# rev2.net
KiCad netlist of a schematic drawn in EAGLE
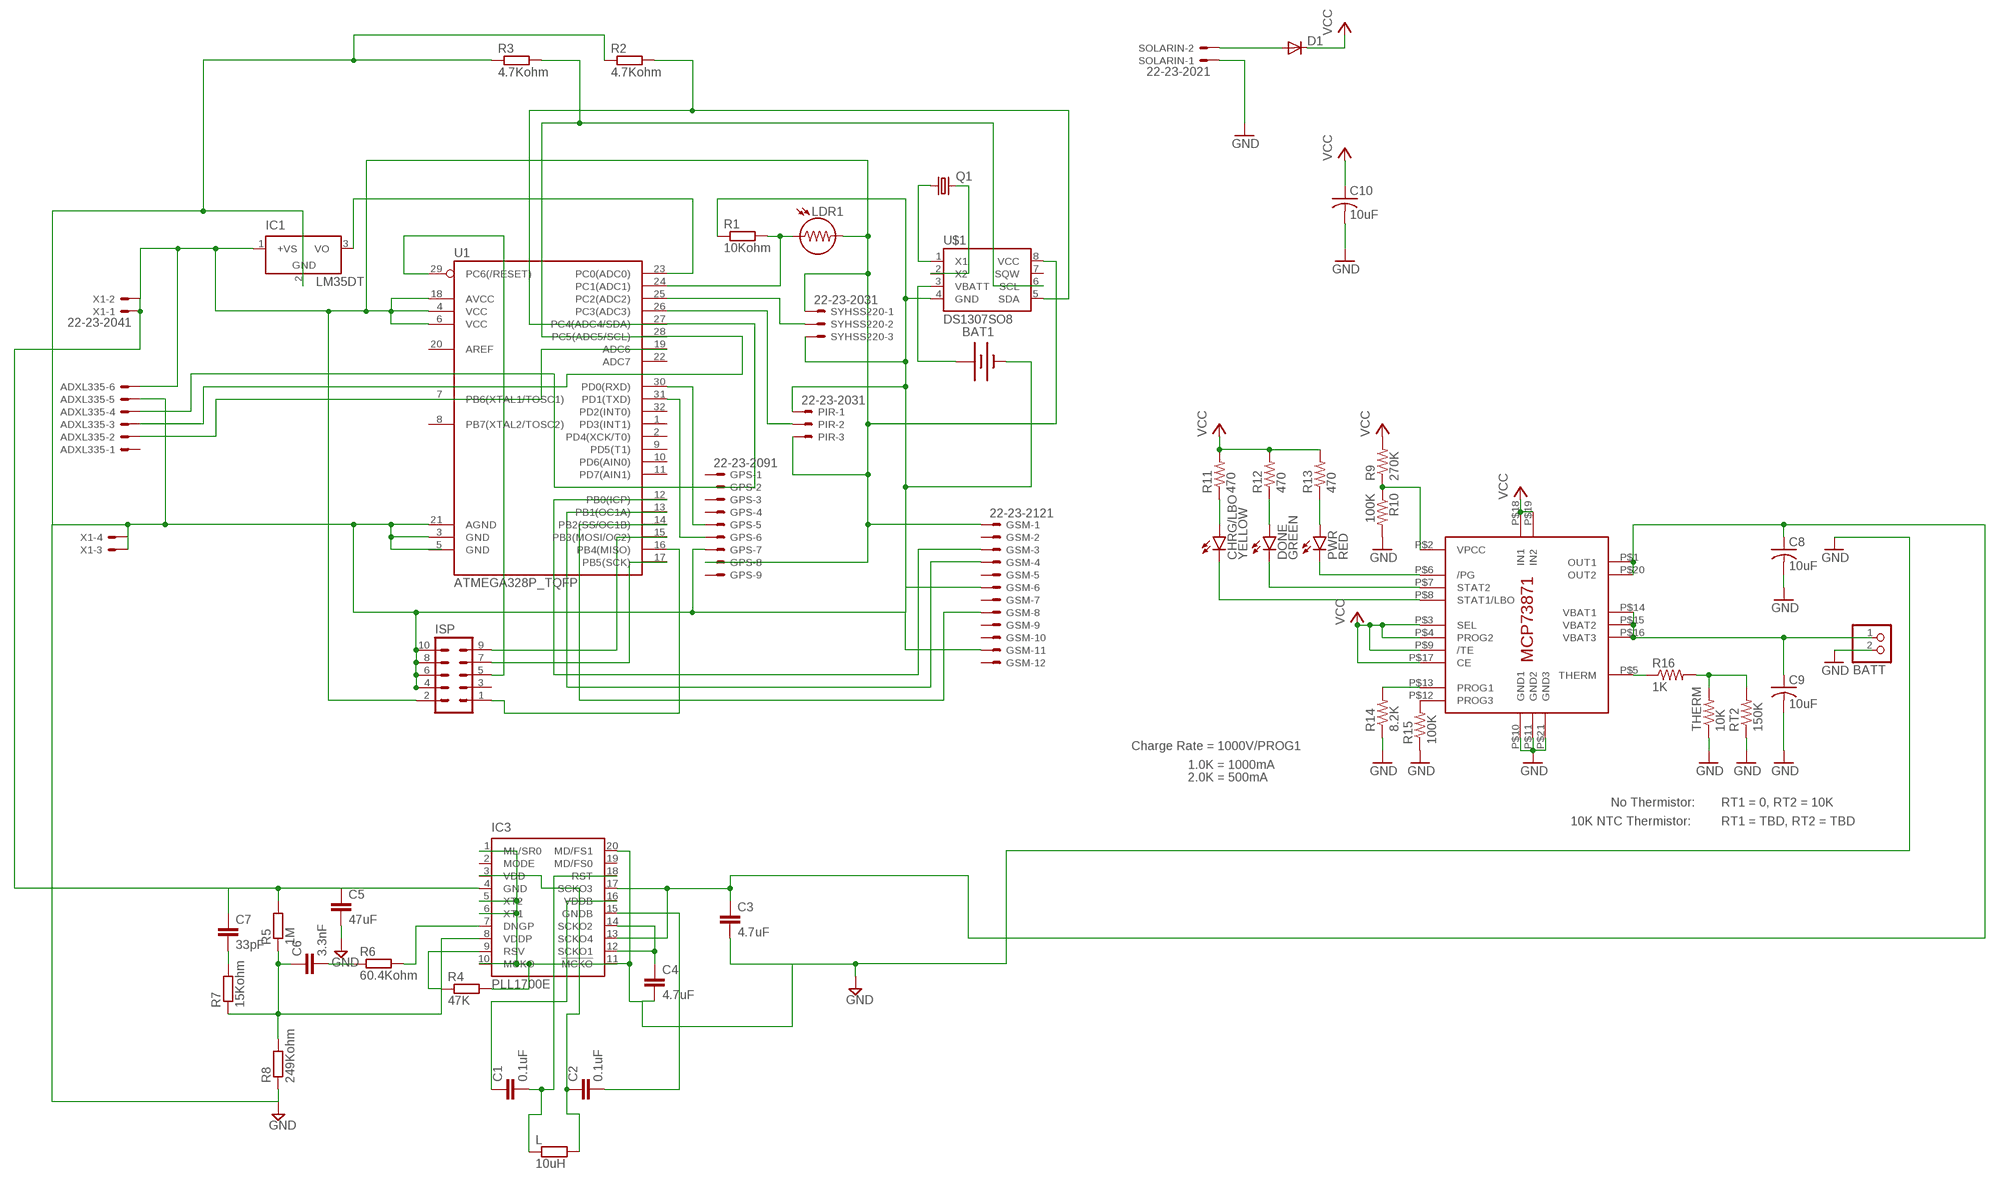
[diagram p0: schematic, sheet 1]

(export (version "E")
  (design (tool "Eeschema 10.0.6"))
  (components
    (comp (ref "ADXL335")
      (value "22-23-2061")
      (footprint "eagle-import:22-23-2061")
      (fields (field (name "MF") "MOLEX"))
      (libsource (lib "eagle-import") (part "22-23-2061"))
    )
    (comp (ref "BAT1")
      (value "BATTERY20PTH")
      (footprint "eagle-import:BATTCOM_20MM_PTH")
      (libsource (lib "eagle-import") (part "BATTERY20PTH"))
    )
    (comp (ref "BATT")
      (value "JST_2PIN-SMT-RA")
      (footprint "eagle-import:JST-PH-2-SMT-RA")
      (libsource (lib "eagle-import") (part "JST_2PIN-SMT-RA"))
    )
    (comp (ref "C1")
      (value "0.1uF")
      (footprint "eagle-import:0402-CAP")
      (libsource (lib "eagle-import") (part "0.1UF-16V(+-10%)(0402)"))
    )
    (comp (ref "C2")
      (value "0.1uF")
      (footprint "eagle-import:0402-CAP")
      (libsource (lib "eagle-import") (part "0.1UF-16V(+-10%)(0402)"))
    )
    (comp (ref "C3")
      (value "4.7uF")
      (footprint "eagle-import:0603-CAP")
      (libsource (lib "eagle-import") (part "4.7UF-6.3V-10%(0603)0603"))
    )
    (comp (ref "C4")
      (value "4.7uF")
      (footprint "eagle-import:0603-CAP")
      (libsource (lib "eagle-import") (part "4.7UF-6.3V-10%(0603)0603"))
    )
    (comp (ref "C5")
      (value "47uF")
      (footprint "eagle-import:0603-CAP")
      (libsource (lib "eagle-import") (part "CAP0603-CAP"))
    )
    (comp (ref "C6")
      (value "3.3nF")
      (footprint "eagle-import:0603-CAP")
      (libsource (lib "eagle-import") (part "3.3NF-100V-10%(0603)"))
    )
    (comp (ref "C7")
      (value "33pF")
      (footprint "eagle-import:0603-CAP")
      (libsource (lib "eagle-import") (part "33PF-50V-5%-(0603)"))
    )
    (comp (ref "C8")
      (value "10uF")
      (footprint "eagle-import:C0805K")
      (libsource (lib "eagle-import") (part "C-USC0805K"))
    )
    (comp (ref "C9")
      (value "10uF")
      (footprint "eagle-import:C0805K")
      (libsource (lib "eagle-import") (part "C-USC0805K"))
    )
    (comp (ref "C10")
      (value "10uF")
      (footprint "eagle-import:C0805K")
      (libsource (lib "eagle-import") (part "C-USC0805K"))
    )
    (comp (ref "CHRG/LBO")
      (value "YELLOW")
      (footprint "eagle-import:LED-1206")
      (libsource (lib "eagle-import") (part "LED-YELLOWLARGE"))
    )
    (comp (ref "D1")
      (value "DIODEPTH")
      (footprint "eagle-import:DIODE-1N4001")
      (libsource (lib "eagle-import") (part "DIODEPTH"))
    )
    (comp (ref "DONE")
      (value "GREEN")
      (footprint "eagle-import:LED-1206")
      (libsource (lib "eagle-import") (part "LED-GREENLARGE"))
    )
    (comp (ref "GPS")
      (value "22-23-2091")
      (footprint "eagle-import:22-23-2091")
      (fields (field (name "MF") "MOLEX"))
      (libsource (lib "eagle-import") (part "22-23-2091"))
    )
    (comp (ref "GSM")
      (value "22-23-2121")
      (footprint "eagle-import:22-23-2121")
      (fields (field (name "MF") "MOLEX"))
      (libsource (lib "eagle-import") (part "22-23-2121"))
    )
    (comp (ref "IC1")
      (value "LM35DT")
      (footprint "eagle-import:TO220V")
      (libsource (lib "eagle-import") (part "LM35DT"))
    )
    (comp (ref "IC2")
      (value "MCP73871")
      (footprint "eagle-import:QFN20_4MM")
      (libsource (lib "eagle-import") (part "MCP73871"))
    )
    (comp (ref "IC3")
      (value "PLL1700E")
      (footprint "eagle-import:SSOP20")
      (fields (field (name "MF") "TEXAS INSTRUMENT CONNECTORS"))
      (libsource (lib "eagle-import") (part "PLL1700E"))
    )
    (comp (ref "ISP")
      (value "ML10")
      (footprint "eagle-import:ML10")
      (libsource (lib "eagle-import") (part "ML10"))
    )
    (comp (ref "L")
      (value "10uH")
      (footprint "eagle-import:R0207_4")
      (libsource (lib "eagle-import") (part "6MM-EU4"))
    )
    (comp (ref "LDR1")
      (value "LDR5MM")
      (footprint "eagle-import:LDR338-54C")
      (libsource (lib "eagle-import") (part "LDR5MM"))
    )
    (comp (ref "PIR")
      (value "22-23-2031")
      (footprint "eagle-import:22-23-2031")
      (fields (field (name "MF") "MOLEX"))
      (libsource (lib "eagle-import") (part "22-23-2031"))
    )
    (comp (ref "PWR")
      (value "RED")
      (footprint "eagle-import:LED-1206")
      (libsource (lib "eagle-import") (part "LED-RED1206"))
    )
    (comp (ref "Q1")
      (value "CRYSTALTC26H")
      (footprint "eagle-import:TC26H")
      (libsource (lib "eagle-import") (part "CRYSTALTC26H"))
    )
    (comp (ref "R1")
      (value "10Kohm")
      (footprint "eagle-import:M1206")
      (libsource (lib "eagle-import") (part "R-EU_M1206"))
    )
    (comp (ref "R2")
      (value "4.7Kohm")
      (footprint "eagle-import:M1206")
      (libsource (lib "eagle-import") (part "R-EU_M1206"))
    )
    (comp (ref "R3")
      (value "4.7Kohm")
      (footprint "eagle-import:M1206")
      (libsource (lib "eagle-import") (part "R-EU_M1206"))
    )
    (comp (ref "R4")
      (value "47K")
      (footprint "eagle-import:M3216")
      (libsource (lib "eagle-import") (part "R-EU_M3216"))
    )
    (comp (ref "R5")
      (value "1M")
      (footprint "eagle-import:M3216")
      (libsource (lib "eagle-import") (part "R-EU_M3216"))
    )
    (comp (ref "R6")
      (value "60.4Kohm")
      (footprint "eagle-import:M3216")
      (libsource (lib "eagle-import") (part "R-EU_M3216"))
    )
    (comp (ref "R7")
      (value "15Kohm")
      (footprint "eagle-import:M1206")
      (libsource (lib "eagle-import") (part "R-EU_M1206"))
    )
    (comp (ref "R8")
      (value "249Kohm")
      (footprint "eagle-import:M1206")
      (libsource (lib "eagle-import") (part "R-EU_M1206"))
    )
    (comp (ref "R9")
      (value "270K")
      (footprint "eagle-import:R0805")
      (libsource (lib "eagle-import") (part "R-US_R0805"))
    )
    (comp (ref "R10")
      (value "100K")
      (footprint "eagle-import:R0805")
      (libsource (lib "eagle-import") (part "R-US_R0805"))
    )
    (comp (ref "R11")
      (value "470")
      (footprint "eagle-import:0603-RES")
      (libsource (lib "eagle-import") (part "470OHM1/10W1%(0603)"))
    )
    (comp (ref "R12")
      (value "470")
      (footprint "eagle-import:0603-RES")
      (libsource (lib "eagle-import") (part "470OHM1/10W1%(0603)"))
    )
    (comp (ref "R13")
      (value "470")
      (footprint "eagle-import:0603-RES")
      (libsource (lib "eagle-import") (part "470OHM1/10W1%(0603)"))
    )
    (comp (ref "R14")
      (value "8.2K")
      (footprint "eagle-import:0603-RES")
      (libsource (lib "eagle-import") (part "8.2KOHM-1/10W-5%(0603)"))
    )
    (comp (ref "R15")
      (value "100K")
      (footprint "eagle-import:R0805")
      (libsource (lib "eagle-import") (part "R-US_R0805"))
    )
    (comp (ref "R16")
      (value "1K")
      (footprint "eagle-import:M0805")
      (libsource (lib "eagle-import") (part "R-US_M0805"))
    )
    (comp (ref "RT2")
      (value "150K")
      (footprint "eagle-import:M0805")
      (libsource (lib "eagle-import") (part "R-US_M0805"))
    )
    (comp (ref "SOLARIN")
      (value "22-23-2021")
      (footprint "eagle-import:22-23-2021")
      (fields (field (name "MF") "MOLEX"))
      (libsource (lib "eagle-import") (part "22-23-2021"))
    )
    (comp (ref "SYHSS220")
      (value "22-23-2031")
      (footprint "eagle-import:22-23-2031")
      (fields (field (name "MF") "MOLEX"))
      (libsource (lib "eagle-import") (part "22-23-2031"))
    )
    (comp (ref "THERM")
      (value "10K")
      (footprint "eagle-import:0805-THM")
      (libsource (lib "eagle-import") (part "R-US_FLIPFLOP"))
    )
    (comp (ref "U$1")
      (value "DS1307SO8")
      (footprint "eagle-import:SO08")
      (libsource (lib "eagle-import") (part "DS1307SO8"))
    )
    (comp (ref "U1")
      (value "ATMEGA328P_TQFP")
      (footprint "eagle-import:TQFP32-08")
      (libsource (lib "eagle-import") (part "ATMEGA328P_TQFP"))
    )
    (comp (ref "X1")
      (value "22-23-2041")
      (footprint "eagle-import:22-23-2041")
      (fields (field (name "MF") "MOLEX"))
      (libsource (lib "eagle-import") (part "22-23-2041"))
    )
  )
  (nets
    (net (code "1") (name "GND") (class "Default")
      (node (ref "ADXL335") (pin "5") (pinfunction "S_5") (pintype "passive"))
      (node (ref "BAT1") (pin "2") (pinfunction "-_2") (pintype "power_in"))
      (node (ref "BATT") (pin "2") (pinfunction "1_2") (pintype "passive"))
      (node (ref "C10") (pin "2") (pinfunction "2_2") (pintype "passive"))
      (node (ref "C3") (pin "2") (pinfunction "2_2") (pintype "passive"))
      (node (ref "C4") (pin "2") (pinfunction "2_2") (pintype "passive"))
      (node (ref "C5") (pin "2") (pinfunction "2_2") (pintype "passive"))
      (node (ref "C8") (pin "2") (pinfunction "2_2") (pintype "passive"))
      (node (ref "C9") (pin "2") (pinfunction "2_2") (pintype "passive"))
      (node (ref "GPS") (pin "7") (pinfunction "S_7") (pintype "passive"))
      (node (ref "GSM") (pin "11") (pinfunction "S_11") (pintype "passive"))
      (node (ref "GSM") (pin "6") (pinfunction "S_6") (pintype "passive"))
      (node (ref "IC1") (pin "2") (pinfunction "GND_2") (pintype "power_in"))
      (node (ref "IC2") (pin "P$10") (pinfunction "GND1_P$10") (pintype "power_in"))
      (node (ref "IC2") (pin "P$11") (pinfunction "GND2_P$11") (pintype "power_in"))
      (node (ref "IC2") (pin "P$21") (pinfunction "GND3_P$21") (pintype "power_in"))
      (node (ref "IC3") (pin "1") (pinfunction "ML/SR0_1") (pintype "input"))
      (node (ref "IC3") (pin "10") (pinfunction "MCKO_10") (pintype "output"))
      (node (ref "IC3") (pin "11") (pinfunction "~{MCKO}_11") (pintype "output"))
      (node (ref "IC3") (pin "20") (pinfunction "MD/FS1_20") (pintype "input"))
      (node (ref "IC3") (pin "5") (pinfunction "XT2_5") (pintype "input"))
      (node (ref "IC3") (pin "6") (pinfunction "XT1_6") (pintype "input"))
      (node (ref "ISP") (pin "10") (pinfunction "10_10") (pintype "passive"))
      (node (ref "ISP") (pin "4") (pinfunction "4_4") (pintype "passive"))
      (node (ref "ISP") (pin "6") (pinfunction "6_6") (pintype "passive"))
      (node (ref "ISP") (pin "8") (pinfunction "8_8") (pintype "passive"))
      (node (ref "PIR") (pin "1") (pinfunction "S_1") (pintype "passive"))
      (node (ref "R1") (pin "1") (pinfunction "1_1") (pintype "passive"))
      (node (ref "R10") (pin "2") (pinfunction "2_2") (pintype "passive"))
      (node (ref "R14") (pin "1") (pinfunction "1_1") (pintype "passive"))
      (node (ref "R15") (pin "1") (pinfunction "1_1") (pintype "passive"))
      (node (ref "R2") (pin "1") (pinfunction "1_1") (pintype "passive"))
      (node (ref "R3") (pin "1") (pinfunction "1_1") (pintype "passive"))
      (node (ref "R4") (pin "2") (pinfunction "2_2") (pintype "passive"))
      (node (ref "R8") (pin "1") (pinfunction "1_1") (pintype "passive"))
      (node (ref "RT2") (pin "1") (pinfunction "1_1") (pintype "passive"))
      (node (ref "SOLARIN") (pin "1") (pinfunction "S_1") (pintype "passive"))
      (node (ref "SYHSS220") (pin "3") (pinfunction "S_3") (pintype "passive"))
      (node (ref "THERM") (pin "1") (pinfunction "1_1") (pintype "passive"))
      (node (ref "U$1") (pin "4") (pinfunction "GND_4") (pintype "bidirectional"))
      (node (ref "U1") (pin "21") (pinfunction "AGND_21") (pintype "bidirectional"))
      (node (ref "U1") (pin "3") (pinfunction "GND_3") (pintype "bidirectional"))
      (node (ref "X1") (pin "3") (pinfunction "S_3") (pintype "passive"))
      (node (ref "X1") (pin "4") (pinfunction "S_4") (pintype "passive"))
    )
    (net (code "2") (name "Net-(ADXL335B-S)") (class "Default")
      (node (ref "ADXL335") (pin "2") (pinfunction "S_2") (pintype "passive"))
      (node (ref "U1") (pin "19") (pinfunction "ADC6_19") (pintype "bidirectional"))
    )
    (net (code "3") (name "Net-(ADXL335C-S)") (class "Default")
      (node (ref "ADXL335") (pin "3") (pinfunction "S_3") (pintype "passive"))
      (node (ref "R3") (pin "2") (pinfunction "2_2") (pintype "passive"))
      (node (ref "U$1") (pin "6") (pinfunction "SCL_6") (pintype "bidirectional"))
      (node (ref "U1") (pin "28") (pinfunction "PC5(ADC5/SCL)_28") (pintype "bidirectional"))
    )
    (net (code "4") (name "Net-(ADXL335D-S)") (class "Default")
      (node (ref "ADXL335") (pin "4") (pinfunction "S_4") (pintype "passive"))
      (node (ref "R2") (pin "2") (pinfunction "2_2") (pintype "passive"))
      (node (ref "U$1") (pin "5") (pinfunction "SDA_5") (pintype "bidirectional"))
      (node (ref "U1") (pin "27") (pinfunction "PC4(ADC4/SDA)_27") (pintype "bidirectional"))
    )
    (net (code "5") (name "Net-(ADXL335F-S)") (class "Default")
      (node (ref "ADXL335") (pin "6") (pinfunction "S_6") (pintype "passive"))
      (node (ref "C5") (pin "1") (pinfunction "1_1") (pintype "passive"))
      (node (ref "C7") (pin "1") (pinfunction "1_1") (pintype "passive"))
      (node (ref "GPS") (pin "8") (pinfunction "S_8") (pintype "passive"))
      (node (ref "GSM") (pin "1") (pinfunction "S_1") (pintype "passive"))
      (node (ref "IC1") (pin "1") (pinfunction "+VS_1") (pintype "input"))
      (node (ref "IC3") (pin "4") (pinfunction "GND_4") (pintype "power_in"))
      (node (ref "ISP") (pin "2") (pinfunction "2_2") (pintype "passive"))
      (node (ref "LDR1") (pin "2") (pinfunction "2_2") (pintype "passive"))
      (node (ref "PIR") (pin "3") (pinfunction "S_3") (pintype "passive"))
      (node (ref "R5") (pin "2") (pinfunction "2_2") (pintype "passive"))
      (node (ref "SYHSS220") (pin "1") (pinfunction "S_1") (pintype "passive"))
      (node (ref "U$1") (pin "8") (pinfunction "VCC_8") (pintype "bidirectional"))
      (node (ref "U1") (pin "18") (pinfunction "AVCC_18") (pintype "bidirectional"))
      (node (ref "U1") (pin "4") (pinfunction "VCC_4") (pintype "bidirectional"))
      (node (ref "U1") (pin "6") (pinfunction "VCC_6") (pintype "bidirectional"))
      (node (ref "X1") (pin "1") (pinfunction "S_1") (pintype "passive"))
      (node (ref "X1") (pin "2") (pinfunction "S_2") (pintype "passive"))
    )
    (net (code "6") (name "Net-(BAT1-+)") (class "Default")
      (node (ref "BAT1") (pin "1") (pinfunction "+_1") (pintype "power_in"))
      (node (ref "U$1") (pin "3") (pinfunction "VBATT_3") (pintype "bidirectional"))
    )
    (net (code "7") (name "Net-(BATT-2)") (class "Default")
      (node (ref "BATT") (pin "1") (pinfunction "2_1") (pintype "passive"))
      (node (ref "C9") (pin "1") (pinfunction "1_1") (pintype "passive"))
      (node (ref "IC2") (pin "P$14") (pinfunction "VBAT1_P$14") (pintype "output"))
      (node (ref "IC2") (pin "P$15") (pinfunction "VBAT2_P$15") (pintype "output"))
      (node (ref "IC2") (pin "P$16") (pinfunction "VBAT3_P$16") (pintype "output"))
    )
    (net (code "8") (name "Net-(C6-Pad2)") (class "Default")
      (node (ref "C6") (pin "2") (pinfunction "2_2") (pintype "passive"))
      (node (ref "R6") (pin "1") (pinfunction "1_1") (pintype "passive"))
    )
    (net (code "9") (name "Net-(C7-Pad2)") (class "Default")
      (node (ref "C7") (pin "2") (pinfunction "2_2") (pintype "passive"))
      (node (ref "R7") (pin "2") (pinfunction "2_2") (pintype "passive"))
    )
    (net (code "10") (name "Net-(CHRG/LBO-PadA)") (class "Default")
      (node (ref "CHRG/LBO") (pin "A") (pinfunction "A_A") (pintype "passive"))
      (node (ref "R11") (pin "1") (pinfunction "1_1") (pintype "passive"))
    )
    (net (code "11") (name "Net-(DONE-PadA)") (class "Default")
      (node (ref "DONE") (pin "A") (pinfunction "A_A") (pintype "passive"))
      (node (ref "R12") (pin "1") (pinfunction "1_1") (pintype "passive"))
    )
    (net (code "12") (name "Net-(GPSE-S)") (class "Default")
      (node (ref "GPS") (pin "5") (pinfunction "S_5") (pintype "passive"))
      (node (ref "U1") (pin "30") (pinfunction "PD0(RXD)_30") (pintype "bidirectional"))
    )
    (net (code "13") (name "Net-(GPSF-S)") (class "Default")
      (node (ref "GPS") (pin "6") (pinfunction "S_6") (pintype "passive"))
      (node (ref "U1") (pin "31") (pinfunction "PD1(TXD)_31") (pintype "bidirectional"))
    )
    (net (code "14") (name "Net-(GSMF-S)") (class "Default")
      (node (ref "GSM") (pin "3") (pinfunction "S_3") (pintype "passive"))
      (node (ref "U1") (pin "12") (pinfunction "PB0(ICP)_12") (pintype "bidirectional"))
    )
    (net (code "15") (name "Net-(GSMG-S)") (class "Default")
      (node (ref "GSM") (pin "4") (pinfunction "S_4") (pintype "passive"))
      (node (ref "U1") (pin "13") (pinfunction "PB1(OC1A)_13") (pintype "bidirectional"))
    )
    (net (code "16") (name "Net-(GSMK-S)") (class "Default")
      (node (ref "GSM") (pin "8") (pinfunction "S_8") (pintype "passive"))
      (node (ref "U1") (pin "14") (pinfunction "PB2(SS/OC1B)_14") (pintype "bidirectional"))
    )
    (net (code "17") (name "Net-(IC1-VO)") (class "Default")
      (node (ref "IC1") (pin "3") (pinfunction "VO_3") (pintype "input"))
      (node (ref "U1") (pin "23") (pinfunction "PC0(ADC0)_23") (pintype "bidirectional"))
    )
    (net (code "18") (name "Net-(IC2-OUT1)") (class "Default")
      (node (ref "C3") (pin "1") (pinfunction "1_1") (pintype "passive"))
      (node (ref "C8") (pin "1") (pinfunction "1_1") (pintype "passive"))
      (node (ref "IC2") (pin "P$1") (pinfunction "OUT1_P$1") (pintype "output"))
      (node (ref "IC2") (pin "P$20") (pinfunction "OUT2_P$20") (pintype "output"))
      (node (ref "IC3") (pin "13") (pinfunction "SCKO4_13") (pintype "output"))
      (node (ref "IC3") (pin "17") (pinfunction "SCKO3_17") (pintype "output"))
    )
    (net (code "19") (name "Net-(IC2-PROG1)") (class "Default")
      (node (ref "IC2") (pin "P$13") (pinfunction "PROG1_P$13") (pintype "input"))
      (node (ref "R14") (pin "2") (pinfunction "2_2") (pintype "passive"))
    )
    (net (code "20") (name "Net-(IC2-PROG3)") (class "Default")
      (node (ref "IC2") (pin "P$12") (pinfunction "PROG3_P$12") (pintype "input"))
      (node (ref "R15") (pin "2") (pinfunction "2_2") (pintype "passive"))
    )
    (net (code "21") (name "Net-(IC2-STAT1{slash}LBO)") (class "Default")
      (node (ref "CHRG/LBO") (pin "C") (pinfunction "C_C") (pintype "passive"))
      (node (ref "IC2") (pin "P$8") (pinfunction "STAT1/LBO_P$8") (pintype "output"))
    )
    (net (code "22") (name "Net-(IC2-STAT2)") (class "Default")
      (node (ref "DONE") (pin "C") (pinfunction "C_C") (pintype "passive"))
      (node (ref "IC2") (pin "P$7") (pinfunction "STAT2_P$7") (pintype "output"))
    )
    (net (code "23") (name "Net-(IC2-THERM)") (class "Default")
      (node (ref "IC2") (pin "P$5") (pinfunction "THERM_P$5") (pintype "input"))
      (node (ref "R16") (pin "1") (pinfunction "1_1") (pintype "passive"))
    )
    (net (code "24") (name "Net-(IC2-VPCC)") (class "Default")
      (node (ref "IC2") (pin "P$2") (pinfunction "VPCC_P$2") (pintype "input"))
      (node (ref "R10") (pin "1") (pinfunction "1_1") (pintype "passive"))
      (node (ref "R9") (pin "1") (pinfunction "1_1") (pintype "passive"))
    )
    (net (code "25") (name "Net-(IC2-{slash}PG)") (class "Default")
      (node (ref "IC2") (pin "P$6") (pinfunction "/PG_P$6") (pintype "output"))
      (node (ref "PWR") (pin "C") (pinfunction "C_C") (pintype "passive"))
    )
    (net (code "26") (name "Net-(IC3-DNGP)") (class "Default")
      (node (ref "IC3") (pin "7") (pinfunction "DNGP_7") (pintype "power_in"))
      (node (ref "R6") (pin "2") (pinfunction "2_2") (pintype "passive"))
    )
    (net (code "27") (name "Net-(IC3-GNDB)") (class "Default")
      (node (ref "C2") (pin "2") (pinfunction "2_2") (pintype "passive"))
      (node (ref "IC3") (pin "15") (pinfunction "GNDB_15") (pintype "power_in"))
    )
    (net (code "28") (name "Net-(IC3-RST)") (class "Default")
      (node (ref "C1") (pin "2") (pinfunction "2_2") (pintype "passive"))
      (node (ref "IC3") (pin "18") (pinfunction "RST_18") (pintype "input"))
      (node (ref "L") (pin "1") (pinfunction "1_1") (pintype "passive"))
    )
    (net (code "29") (name "Net-(IC3-RSV)") (class "Default")
      (node (ref "IC3") (pin "9") (pinfunction "RSV_9") (pintype "passive"))
      (node (ref "R4") (pin "1") (pinfunction "1_1") (pintype "passive"))
    )
    (net (code "30") (name "Net-(IC3-SCKO1)") (class "Default")
      (node (ref "C4") (pin "1") (pinfunction "1_1") (pintype "passive"))
      (node (ref "IC3") (pin "12") (pinfunction "SCKO1_12") (pintype "output"))
      (node (ref "IC3") (pin "14") (pinfunction "SCKO2_14") (pintype "output"))
    )
    (net (code "31") (name "Net-(IC3-VDD)") (class "Default")
      (node (ref "C2") (pin "1") (pinfunction "1_1") (pintype "passive"))
      (node (ref "IC3") (pin "3") (pinfunction "VDD_3") (pintype "input"))
      (node (ref "L") (pin "2") (pinfunction "2_2") (pintype "passive"))
    )
    (net (code "32") (name "Net-(IC3-VDDB)") (class "Default")
      (node (ref "C1") (pin "1") (pinfunction "1_1") (pintype "passive"))
      (node (ref "IC3") (pin "16") (pinfunction "VDDB_16") (pintype "power_in"))
    )
    (net (code "33") (name "Net-(IC3-VDDP)") (class "Default")
      (node (ref "C6") (pin "1") (pinfunction "1_1") (pintype "passive"))
      (node (ref "IC3") (pin "8") (pinfunction "VDDP_8") (pintype "power_in"))
      (node (ref "R5") (pin "1") (pinfunction "1_1") (pintype "passive"))
      (node (ref "R7") (pin "1") (pinfunction "1_1") (pintype "passive"))
      (node (ref "R8") (pin "2") (pinfunction "2_2") (pintype "passive"))
    )
    (net (code "34") (name "Net-(PIRB-S)") (class "Default")
      (node (ref "PIR") (pin "2") (pinfunction "S_2") (pintype "passive"))
      (node (ref "U1") (pin "26") (pinfunction "PC3(ADC3)_26") (pintype "bidirectional"))
    )
    (net (code "35") (name "Net-(PWR-PadA)") (class "Default")
      (node (ref "PWR") (pin "A") (pinfunction "A_A") (pintype "passive"))
      (node (ref "R13") (pin "1") (pinfunction "1_1") (pintype "passive"))
    )
    (net (code "36") (name "Net-(R16-Pad2)") (class "Default")
      (node (ref "R16") (pin "2") (pinfunction "2_2") (pintype "passive"))
      (node (ref "RT2") (pin "2") (pinfunction "2_2") (pintype "passive"))
      (node (ref "THERM") (pin "2") (pinfunction "2_2") (pintype "passive"))
    )
    (net (code "37") (name "Net-(SOLARINB-S)") (class "Default")
      (node (ref "D1") (pin "A") (pinfunction "A_A") (pintype "passive"))
      (node (ref "SOLARIN") (pin "2") (pinfunction "S_2") (pintype "passive"))
    )
    (net (code "38") (name "Net-(SYHSS220B-S)") (class "Default")
      (node (ref "SYHSS220") (pin "2") (pinfunction "S_2") (pintype "passive"))
      (node (ref "U1") (pin "25") (pinfunction "PC2(ADC2)_25") (pintype "bidirectional"))
    )
    (net (code "39") (name "Net-(U$1-X1)") (class "Default")
      (node (ref "Q1") (pin "1") (pinfunction "1_1") (pintype "passive"))
      (node (ref "U$1") (pin "1") (pinfunction "X1_1") (pintype "bidirectional"))
    )
    (net (code "40") (name "Net-(U$1-X2)") (class "Default")
      (node (ref "Q1") (pin "2") (pinfunction "2_2") (pintype "passive"))
      (node (ref "U$1") (pin "2") (pinfunction "X2_2") (pintype "bidirectional"))
    )
    (net (code "41") (name "Net-(U1-PB3(MOSI{slash}OC2))") (class "Default")
      (node (ref "ISP") (pin "9") (pinfunction "9_9") (pintype "passive"))
      (node (ref "U1") (pin "15") (pinfunction "PB3(MOSI/OC2)_15") (pintype "bidirectional"))
    )
    (net (code "42") (name "Net-(U1-PB4(MISO))") (class "Default")
      (node (ref "ISP") (pin "1") (pinfunction "1_1") (pintype "passive"))
      (node (ref "U1") (pin "16") (pinfunction "PB4(MISO)_16") (pintype "bidirectional"))
    )
    (net (code "43") (name "Net-(U1-PB5(SCK))") (class "Default")
      (node (ref "ISP") (pin "7") (pinfunction "7_7") (pintype "passive"))
      (node (ref "U1") (pin "17") (pinfunction "PB5(SCK)_17") (pintype "bidirectional"))
    )
    (net (code "44") (name "Net-(U1-PC1(ADC1))") (class "Default")
      (node (ref "LDR1") (pin "1") (pinfunction "1_1") (pintype "passive"))
      (node (ref "R1") (pin "2") (pinfunction "2_2") (pintype "passive"))
      (node (ref "U1") (pin "24") (pinfunction "PC1(ADC1)_24") (pintype "bidirectional"))
    )
    (net (code "45") (name "Net-(U1-PC6({slash}RESET))") (class "Default")
      (node (ref "ISP") (pin "5") (pinfunction "5_5") (pintype "passive"))
      (node (ref "U1") (pin "29") (pinfunction "PC6(/RESET)_29") (pintype "bidirectional"))
    )
    (net (code "46") (name "VCC") (class "Default")
      (node (ref "C10") (pin "1") (pinfunction "1_1") (pintype "passive"))
      (node (ref "D1") (pin "C") (pinfunction "C_C") (pintype "passive"))
      (node (ref "IC2") (pin "P$17") (pinfunction "CE_P$17") (pintype "input"))
      (node (ref "IC2") (pin "P$18") (pinfunction "IN1_P$18") (pintype "input"))
      (node (ref "IC2") (pin "P$19") (pinfunction "IN2_P$19") (pintype "input"))
      (node (ref "IC2") (pin "P$3") (pinfunction "SEL_P$3") (pintype "input"))
      (node (ref "IC2") (pin "P$4") (pinfunction "PROG2_P$4") (pintype "input"))
      (node (ref "IC2") (pin "P$9") (pinfunction "/TE_P$9") (pintype "input"))
      (node (ref "R11") (pin "2") (pinfunction "2_2") (pintype "passive"))
      (node (ref "R12") (pin "2") (pinfunction "2_2") (pintype "passive"))
      (node (ref "R13") (pin "2") (pinfunction "2_2") (pintype "passive"))
      (node (ref "R9") (pin "2") (pinfunction "2_2") (pintype "passive"))
    )
    (net (code "47") (name "unconnected-(ADXL335A-S-Pad1)") (class "Default")
      (node (ref "ADXL335") (pin "1") (pinfunction "S_1") (pintype "passive"))
    )
    (net (code "48") (name "unconnected-(GPSA-S-Pad1)") (class "Default")
      (node (ref "GPS") (pin "1") (pinfunction "S_1") (pintype "passive"))
    )
    (net (code "49") (name "unconnected-(GPSB-S-Pad2)") (class "Default")
      (node (ref "GPS") (pin "2") (pinfunction "S_2") (pintype "passive"))
    )
    (net (code "50") (name "unconnected-(GPSC-S-Pad3)") (class "Default")
      (node (ref "GPS") (pin "3") (pinfunction "S_3") (pintype "passive"))
    )
    (net (code "51") (name "unconnected-(GPSD-S-Pad4)") (class "Default")
      (node (ref "GPS") (pin "4") (pinfunction "S_4") (pintype "passive"))
    )
    (net (code "52") (name "unconnected-(GPSI-S-Pad9)") (class "Default")
      (node (ref "GPS") (pin "9") (pinfunction "S_9") (pintype "passive"))
    )
    (net (code "53") (name "unconnected-(GSMB-S-Pad10)") (class "Default")
      (node (ref "GSM") (pin "10") (pinfunction "S_10") (pintype "passive"))
    )
    (net (code "54") (name "unconnected-(GSMD-S-Pad12)") (class "Default")
      (node (ref "GSM") (pin "12") (pinfunction "S_12") (pintype "passive"))
    )
    (net (code "55") (name "unconnected-(GSME-S-Pad2)") (class "Default")
      (node (ref "GSM") (pin "2") (pinfunction "S_2") (pintype "passive"))
    )
    (net (code "56") (name "unconnected-(GSMH-S-Pad5)") (class "Default")
      (node (ref "GSM") (pin "5") (pinfunction "S_5") (pintype "passive"))
    )
    (net (code "57") (name "unconnected-(GSMJ-S-Pad7)") (class "Default")
      (node (ref "GSM") (pin "7") (pinfunction "S_7") (pintype "passive"))
    )
    (net (code "58") (name "unconnected-(GSML-S-Pad9)") (class "Default")
      (node (ref "GSM") (pin "9") (pinfunction "S_9") (pintype "passive"))
    )
    (net (code "59") (name "unconnected-(IC3-MD{slash}FS0-Pad19)") (class "Default")
      (node (ref "IC3") (pin "19") (pinfunction "MD/FS0_19") (pintype "input"))
    )
    (net (code "60") (name "unconnected-(IC3-MODE-Pad2)") (class "Default")
      (node (ref "IC3") (pin "2") (pinfunction "MODE_2") (pintype "input"))
    )
    (net (code "61") (name "unconnected-(ISP-Pad3)") (class "Default")
      (node (ref "ISP") (pin "3") (pinfunction "3_3") (pintype "passive"))
    )
    (net (code "62") (name "unconnected-(U$1-SQW-Pad7)") (class "Default")
      (node (ref "U$1") (pin "7") (pinfunction "SQW_7") (pintype "bidirectional"))
    )
    (net (code "63") (name "unconnected-(U1-ADC7-Pad22)") (class "Default")
      (node (ref "U1") (pin "22") (pinfunction "ADC7_22") (pintype "bidirectional"))
    )
    (net (code "64") (name "unconnected-(U1-AREF-Pad20)") (class "Default")
      (node (ref "U1") (pin "20") (pinfunction "AREF_20") (pintype "bidirectional"))
    )
    (net (code "65") (name "unconnected-(U1-GND-Pad5)") (class "Default")
      (node (ref "U1") (pin "5") (pinfunction "GND_5") (pintype "bidirectional"))
    )
    (net (code "66") (name "unconnected-(U1-PB6(XTAL1{slash}TOSC1)-Pad7)") (class "Default")
      (node (ref "U1") (pin "7") (pinfunction "PB6(XTAL1/TOSC1)_7") (pintype "bidirectional"))
    )
    (net (code "67") (name "unconnected-(U1-PB7(XTAL2{slash}TOSC2)-Pad8)") (class "Default")
      (node (ref "U1") (pin "8") (pinfunction "PB7(XTAL2/TOSC2)_8") (pintype "bidirectional"))
    )
    (net (code "68") (name "unconnected-(U1-PD2(INT0)-Pad32)") (class "Default")
      (node (ref "U1") (pin "32") (pinfunction "PD2(INT0)_32") (pintype "bidirectional"))
    )
    (net (code "69") (name "unconnected-(U1-PD3(INT1)-Pad1)") (class "Default")
      (node (ref "U1") (pin "1") (pinfunction "PD3(INT1)_1") (pintype "bidirectional"))
    )
    (net (code "70") (name "unconnected-(U1-PD4(XCK{slash}T0)-Pad2)") (class "Default")
      (node (ref "U1") (pin "2") (pinfunction "PD4(XCK/T0)_2") (pintype "bidirectional"))
    )
    (net (code "71") (name "unconnected-(U1-PD5(T1)-Pad9)") (class "Default")
      (node (ref "U1") (pin "9") (pinfunction "PD5(T1)_9") (pintype "bidirectional"))
    )
    (net (code "72") (name "unconnected-(U1-PD6(AIN0)-Pad10)") (class "Default")
      (node (ref "U1") (pin "10") (pinfunction "PD6(AIN0)_10") (pintype "bidirectional"))
    )
    (net (code "73") (name "unconnected-(U1-PD7(AIN1)-Pad11)") (class "Default")
      (node (ref "U1") (pin "11") (pinfunction "PD7(AIN1)_11") (pintype "bidirectional"))
    )
  )
)
